# DCDC-BASE-X2A.net
KiCad netlist of a schematic drawn in EAGLE
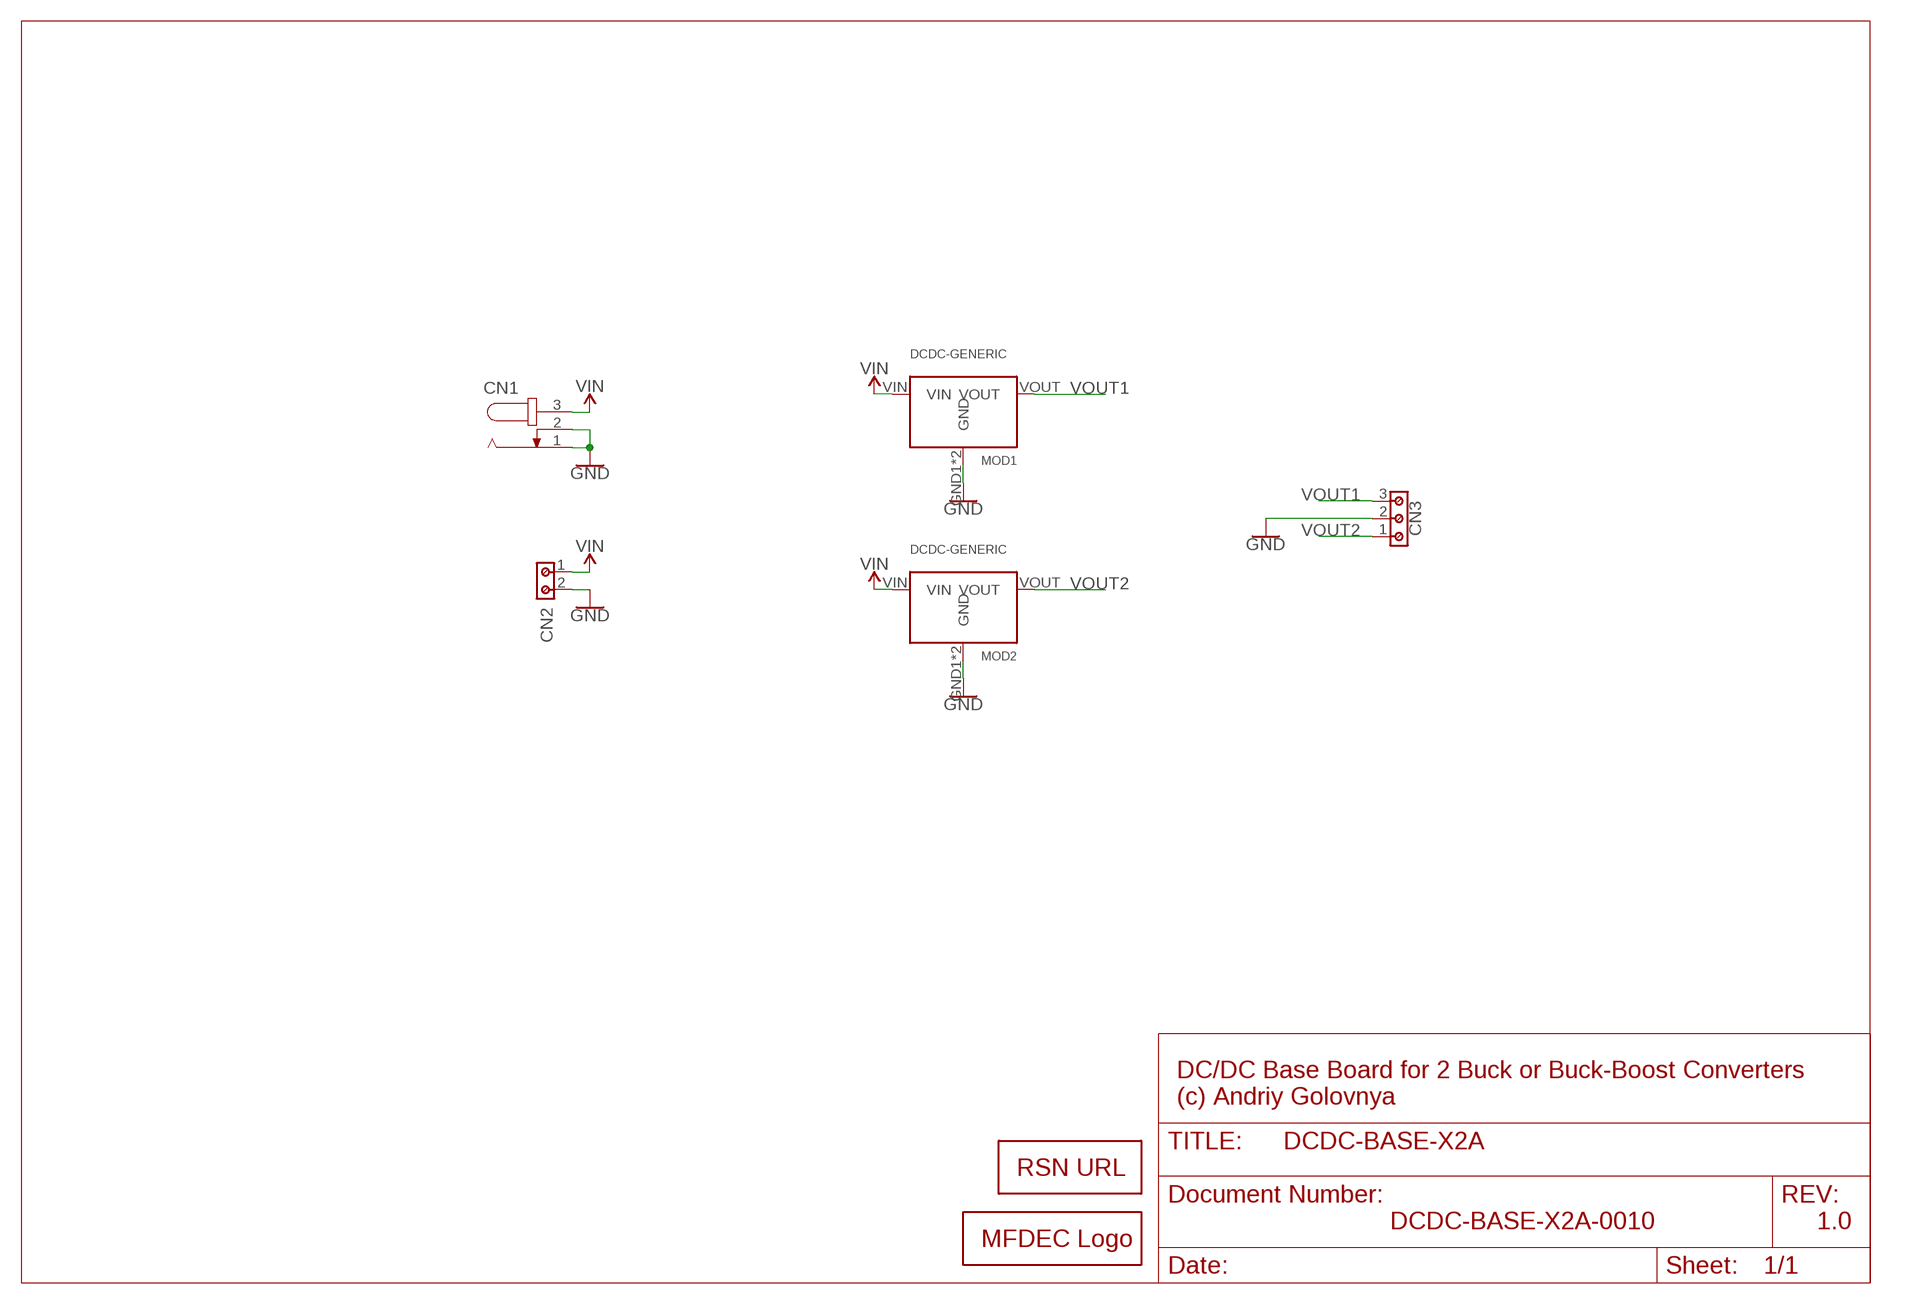
[diagram p0: schematic, sheet 1]

(export (version "E")
  (design (tool "Eeschema 10.0.6"))
  (components
    (comp (ref "CN1")
      (value "JACK-PLUG1")
      (footprint "eagle-import:SPC4078")
      (libsource (lib "eagle-import") (part "JACK-PLUG1"))
    )
    (comp (ref "CN2")
      (value "691213510002")
      (footprint "eagle-import:691213510002")
      (libsource (lib "eagle-import") (part "691213510002"))
    )
    (comp (ref "CN3")
      (value "691213510003")
      (footprint "eagle-import:691213510003")
      (libsource (lib "eagle-import") (part "691213510003"))
    )
    (comp (ref "LOGO1")
      (value "RSNURL_QR_8MM")
      (footprint "eagle-import:RSNURL_QR_8MM")
      (libsource (lib "eagle-import") (part "RSNURL_QR_8MM"))
    )
    (comp (ref "LOGO2")
      (value "MFDECLOGO_L_10MM")
      (footprint "eagle-import:MFDEC_L_10MM")
      (libsource (lib "eagle-import") (part "MFDECLOGO_L_10MM"))
    )
    (comp (ref "MOD1")
      (value "DCDC-GENERIC")
      (footprint "eagle-import:DCDC-BOARD")
      (libsource (lib "eagle-import") (part "DCDC-GENERIC"))
    )
    (comp (ref "MOD2")
      (value "DCDC-GENERIC")
      (footprint "eagle-import:DCDC-BOARD")
      (libsource (lib "eagle-import") (part "DCDC-GENERIC"))
    )
  )
  (nets
    (net (code "1") (name "/VOUT1") (class "Default")
      (node (ref "CN3") (pin "3") (pinfunction "3_3") (pintype "passive"))
      (node (ref "MOD1") (pin "VOUT") (pinfunction "VOUT_VOUT") (pintype "bidirectional"))
    )
    (net (code "2") (name "/VOUT2") (class "Default")
      (node (ref "CN3") (pin "1") (pinfunction "1_1") (pintype "passive"))
      (node (ref "MOD2") (pin "VOUT") (pinfunction "VOUT_VOUT") (pintype "bidirectional"))
    )
    (net (code "3") (name "GND") (class "Default")
      (node (ref "CN1") (pin "1") (pinfunction "1_1") (pintype "passive"))
      (node (ref "CN1") (pin "2") (pinfunction "2_2") (pintype "passive"))
      (node (ref "CN2") (pin "2") (pinfunction "2_2") (pintype "passive"))
      (node (ref "CN3") (pin "2") (pinfunction "2_2") (pintype "passive"))
      (node (ref "MOD1") (pin "GND1") (pinfunction "GND_GND1") (pintype "bidirectional"))
      (node (ref "MOD1") (pin "GND2") (pinfunction "GND_GND2") (pintype "bidirectional"))
      (node (ref "MOD2") (pin "GND1") (pinfunction "GND_GND1") (pintype "bidirectional"))
      (node (ref "MOD2") (pin "GND2") (pinfunction "GND_GND2") (pintype "bidirectional"))
    )
    (net (code "4") (name "VIN") (class "Default")
      (node (ref "CN1") (pin "3") (pinfunction "3_3") (pintype "passive"))
      (node (ref "CN2") (pin "1") (pinfunction "1_1") (pintype "passive"))
      (node (ref "MOD1") (pin "VIN") (pinfunction "VIN_VIN") (pintype "bidirectional"))
      (node (ref "MOD2") (pin "VIN") (pinfunction "VIN_VIN") (pintype "bidirectional"))
    )
  )
)
